# magnet-motor-encoder_v1.net
KiCad netlist of a schematic drawn in EAGLE
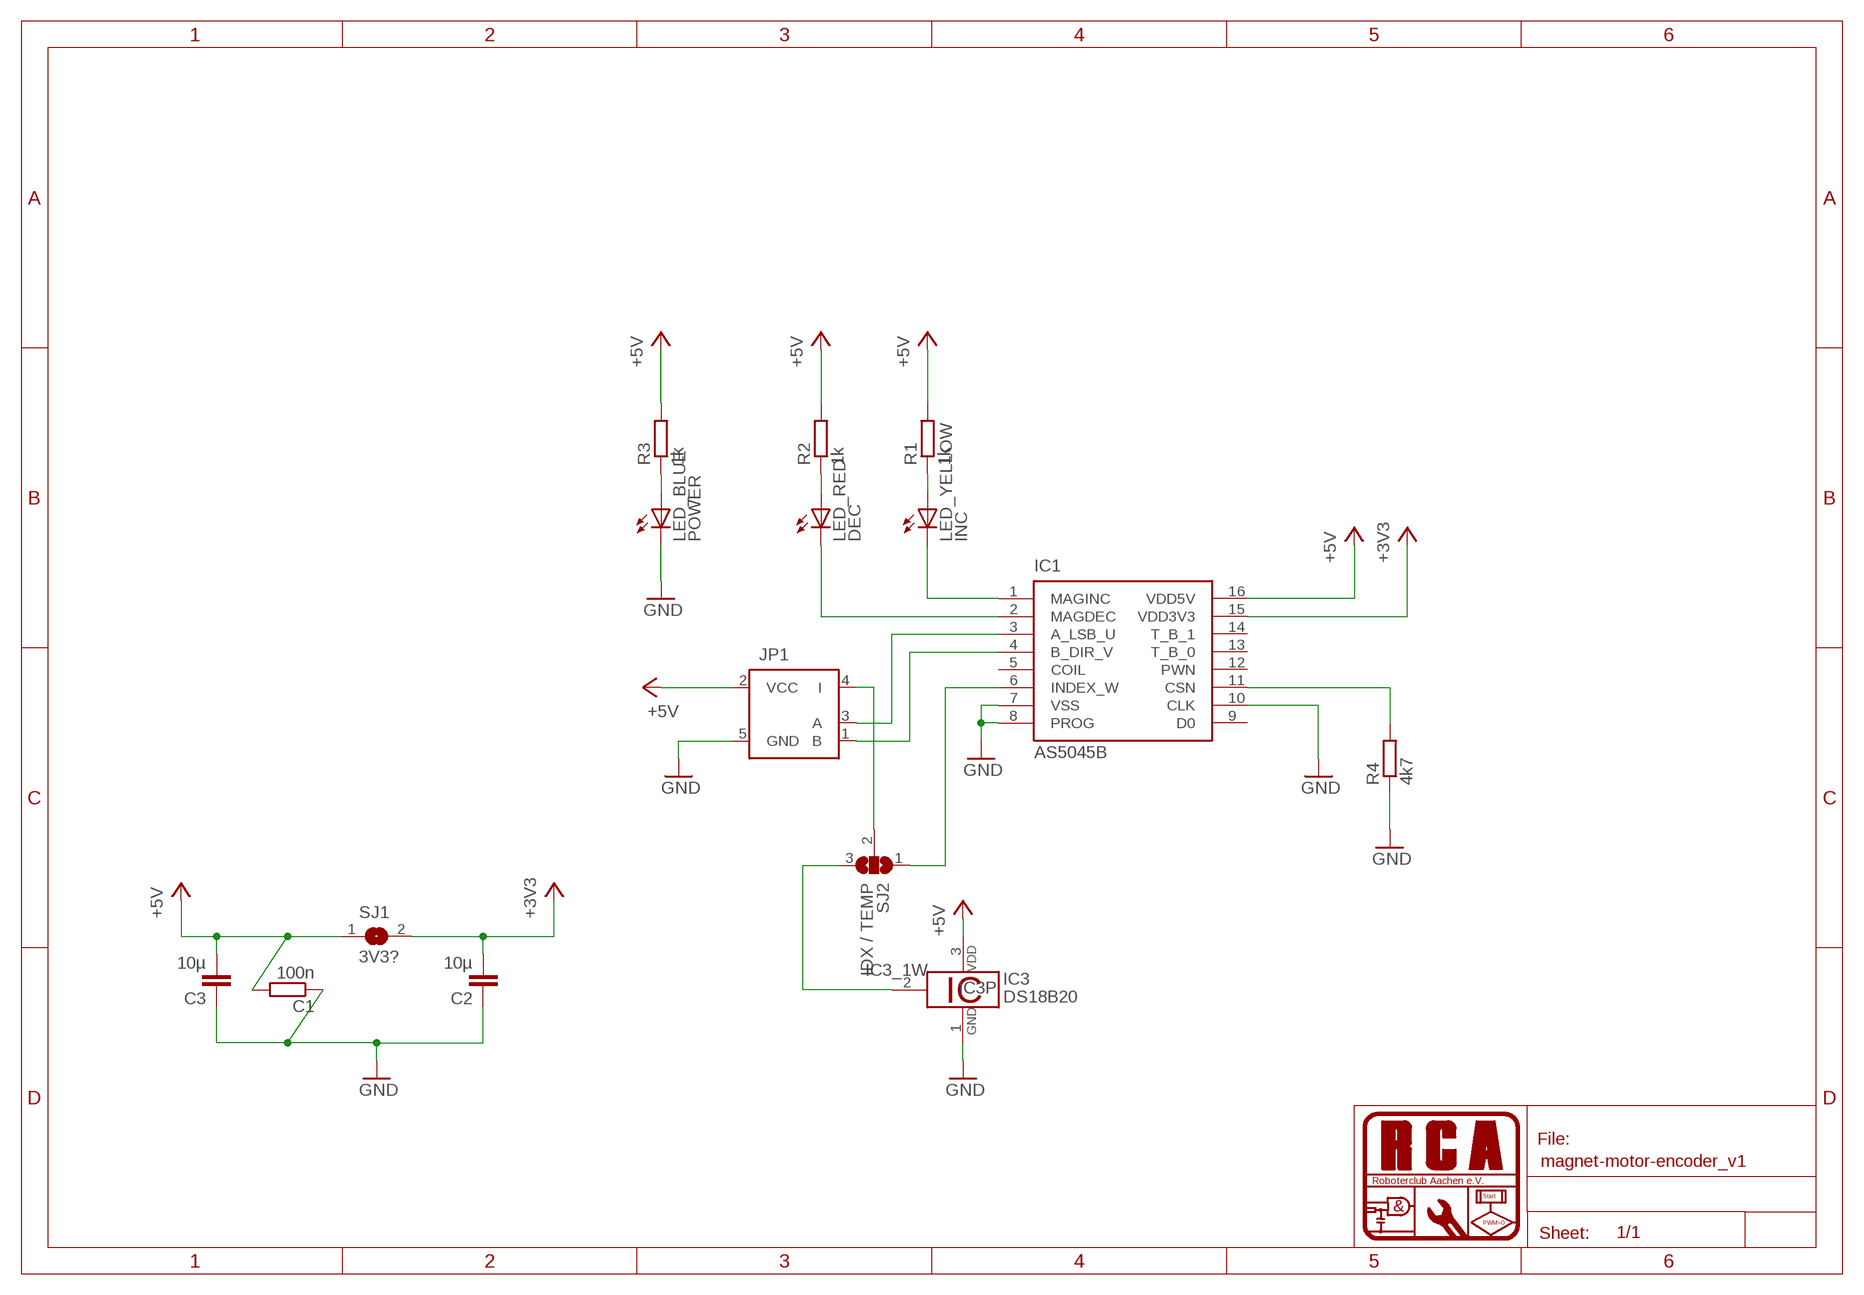
[diagram p0: schematic, sheet 1]

(export (version "E")
  (design (tool "Eeschema 10.0.6"))
  (components
    (comp (ref "C1")
      (value "100n")
      (footprint "eagle-import:R0603")
      (libsource (lib "eagle-import") (part "R-EU_R0603"))
    )
    (comp (ref "C2")
      (value "10µ")
      (footprint "eagle-import:C0805K")
      (libsource (lib "eagle-import") (part "C-EUC0805K"))
    )
    (comp (ref "C3")
      (value "10µ")
      (footprint "eagle-import:C0805K")
      (libsource (lib "eagle-import") (part "C-EUC0805K"))
    )
    (comp (ref "IC1")
      (value "AS5045B")
      (footprint "eagle-import:SSOP16")
      (fields (field (name "MPN") "AS5040ASSU"))
      (libsource (lib "eagle-import") (part "AS5040"))
    )
    (comp (ref "IC3")
      (value "DS18B20")
      (footprint "eagle-import:TO92-")
      (libsource (lib "eagle-import") (part "DS18S20"))
    )
    (comp (ref "JP1")
      (value "ENCODERPSS")
      (footprint "eagle-import:22-23-2051")
      (libsource (lib "eagle-import") (part "ENCODERPSS"))
    )
    (comp (ref "LED_BLUE")
      (value "POWER")
      (footprint "eagle-import:CHIPLED_0805")
      (libsource (lib "eagle-import") (part "LEDCHIPLED_0805"))
    )
    (comp (ref "LED_RED")
      (value "DEC")
      (footprint "eagle-import:CHIPLED_0805")
      (libsource (lib "eagle-import") (part "LEDCHIPLED_0805"))
    )
    (comp (ref "LED_YELLOW")
      (value "INC")
      (footprint "eagle-import:CHIPLED_0805")
      (libsource (lib "eagle-import") (part "LEDCHIPLED_0805"))
    )
    (comp (ref "R1")
      (value "1k")
      (footprint "eagle-import:R0805")
      (libsource (lib "eagle-import") (part "resistor_R-EU_R0805"))
    )
    (comp (ref "R2")
      (value "1k")
      (footprint "eagle-import:R0805")
      (libsource (lib "eagle-import") (part "resistor_R-EU_R0805"))
    )
    (comp (ref "R3")
      (value "1k")
      (footprint "eagle-import:R0805")
      (libsource (lib "eagle-import") (part "resistor_R-EU_R0805"))
    )
    (comp (ref "R4")
      (value "4k7")
      (footprint "eagle-import:R0805")
      (libsource (lib "eagle-import") (part "resistor_R-EU_R0805"))
    )
    (comp (ref "SJ1")
      (value "3V3?")
      (footprint "eagle-import:SJS")
      (libsource (lib "eagle-import") (part "SJS"))
    )
    (comp (ref "SJ2")
      (value "IDX / TEMP")
      (footprint "eagle-import:SJ_2")
      (libsource (lib "eagle-import") (part "SJ2W"))
    )
  )
  (nets
    (net (code "1") (name "+3V3") (class "Default")
      (node (ref "C2") (pin "2") (pinfunction "2_2") (pintype "passive"))
      (node (ref "IC1") (pin "15") (pinfunction "VDD3V3_15") (pintype "passive"))
      (node (ref "SJ1") (pin "2") (pinfunction "2_2") (pintype "passive"))
    )
    (net (code "2") (name "+5V") (class "Default")
      (node (ref "C1") (pin "2") (pinfunction "2_2") (pintype "passive"))
      (node (ref "C3") (pin "2") (pinfunction "2_2") (pintype "passive"))
      (node (ref "IC1") (pin "16") (pinfunction "VDD5V_16") (pintype "passive"))
      (node (ref "IC3") (pin "3") (pinfunction "VDD_3") (pintype "power_in"))
      (node (ref "JP1") (pin "2") (pinfunction "VCC_2") (pintype "power_in"))
      (node (ref "R1") (pin "2") (pinfunction "2_2") (pintype "passive"))
      (node (ref "R2") (pin "2") (pinfunction "2_2") (pintype "passive"))
      (node (ref "R3") (pin "2") (pinfunction "2_2") (pintype "passive"))
      (node (ref "SJ1") (pin "1") (pinfunction "1_1") (pintype "passive"))
    )
    (net (code "3") (name "GND") (class "Default")
      (node (ref "C1") (pin "1") (pinfunction "1_1") (pintype "passive"))
      (node (ref "C2") (pin "1") (pinfunction "1_1") (pintype "passive"))
      (node (ref "C3") (pin "1") (pinfunction "1_1") (pintype "passive"))
      (node (ref "IC1") (pin "10") (pinfunction "CLK_10") (pintype "input"))
      (node (ref "IC1") (pin "7") (pinfunction "VSS_7") (pintype "passive"))
      (node (ref "IC1") (pin "8") (pinfunction "PROG_8") (pintype "input"))
      (node (ref "IC3") (pin "1") (pinfunction "GND_1") (pintype "power_in"))
      (node (ref "JP1") (pin "5") (pinfunction "GND_5") (pintype "power_in"))
      (node (ref "LED_BLUE") (pin "C") (pinfunction "C_C") (pintype "passive"))
      (node (ref "R4") (pin "1") (pinfunction "1_1") (pintype "passive"))
    )
    (net (code "4") (name "Net-(IC1-A_LSB_U)") (class "Default")
      (node (ref "IC1") (pin "3") (pinfunction "A_LSB_U_3") (pintype "output"))
      (node (ref "JP1") (pin "3") (pinfunction "A_3") (pintype "output"))
    )
    (net (code "5") (name "Net-(IC1-B_DIR_V)") (class "Default")
      (node (ref "IC1") (pin "4") (pinfunction "B_DIR_V_4") (pintype "output"))
      (node (ref "JP1") (pin "1") (pinfunction "B_1") (pintype "output"))
    )
    (net (code "6") (name "Net-(IC1-CSN)") (class "Default")
      (node (ref "IC1") (pin "11") (pinfunction "CSN_11") (pintype "input"))
      (node (ref "R4") (pin "2") (pinfunction "2_2") (pintype "passive"))
    )
    (net (code "7") (name "Net-(IC1-INDEX_W)") (class "Default")
      (node (ref "IC1") (pin "6") (pinfunction "INDEX_W_6") (pintype "output"))
      (node (ref "SJ2") (pin "1") (pinfunction "1_1") (pintype "passive"))
    )
    (net (code "8") (name "Net-(IC1-MAGDEC)") (class "Default")
      (node (ref "IC1") (pin "2") (pinfunction "MAGDEC_2") (pintype "tri_state"))
      (node (ref "LED_RED") (pin "C") (pinfunction "C_C") (pintype "passive"))
    )
    (net (code "9") (name "Net-(IC1-MAGINC)") (class "Default")
      (node (ref "IC1") (pin "1") (pinfunction "MAGINC_1") (pintype "tri_state"))
      (node (ref "LED_YELLOW") (pin "C") (pinfunction "C_C") (pintype "passive"))
    )
    (net (code "10") (name "Net-(IC3C-1W)") (class "Default")
      (node (ref "IC3") (pin "2") (pinfunction "1W_2") (pintype "power_in"))
      (node (ref "SJ2") (pin "3") (pinfunction "3_3") (pintype "passive"))
    )
    (net (code "11") (name "Net-(JP1-I)") (class "Default")
      (node (ref "JP1") (pin "4") (pinfunction "I_4") (pintype "output"))
      (node (ref "SJ2") (pin "2") (pinfunction "2_2") (pintype "passive"))
    )
    (net (code "12") (name "Net-(LED_BLUE-PadA)") (class "Default")
      (node (ref "LED_BLUE") (pin "A") (pinfunction "A_A") (pintype "passive"))
      (node (ref "R3") (pin "1") (pinfunction "1_1") (pintype "passive"))
    )
    (net (code "13") (name "Net-(LED_RED-PadA)") (class "Default")
      (node (ref "LED_RED") (pin "A") (pinfunction "A_A") (pintype "passive"))
      (node (ref "R2") (pin "1") (pinfunction "1_1") (pintype "passive"))
    )
    (net (code "14") (name "Net-(LED_YELLOW-PadA)") (class "Default")
      (node (ref "LED_YELLOW") (pin "A") (pinfunction "A_A") (pintype "passive"))
      (node (ref "R1") (pin "1") (pinfunction "1_1") (pintype "passive"))
    )
    (net (code "15") (name "unconnected-(IC1-COIL-Pad5)") (class "Default")
      (node (ref "IC1") (pin "5") (pinfunction "COIL_5") (pintype "no_connect"))
    )
    (net (code "16") (name "unconnected-(IC1-D0-Pad9)") (class "Default")
      (node (ref "IC1") (pin "9") (pinfunction "D0_9") (pintype "tri_state"))
    )
    (net (code "17") (name "unconnected-(IC1-PWN-Pad12)") (class "Default")
      (node (ref "IC1") (pin "12") (pinfunction "PWN_12") (pintype "passive"))
    )
    (net (code "18") (name "unconnected-(IC1-T_B_0-Pad13)") (class "Default")
      (node (ref "IC1") (pin "13") (pinfunction "T_B_0_13") (pintype "no_connect"))
    )
    (net (code "19") (name "unconnected-(IC1-T_B_1-Pad14)") (class "Default")
      (node (ref "IC1") (pin "14") (pinfunction "T_B_1_14") (pintype "no_connect"))
    )
  )
)
